# Inverting_LM741.net
KiCad netlist of a schematic drawn in EAGLE
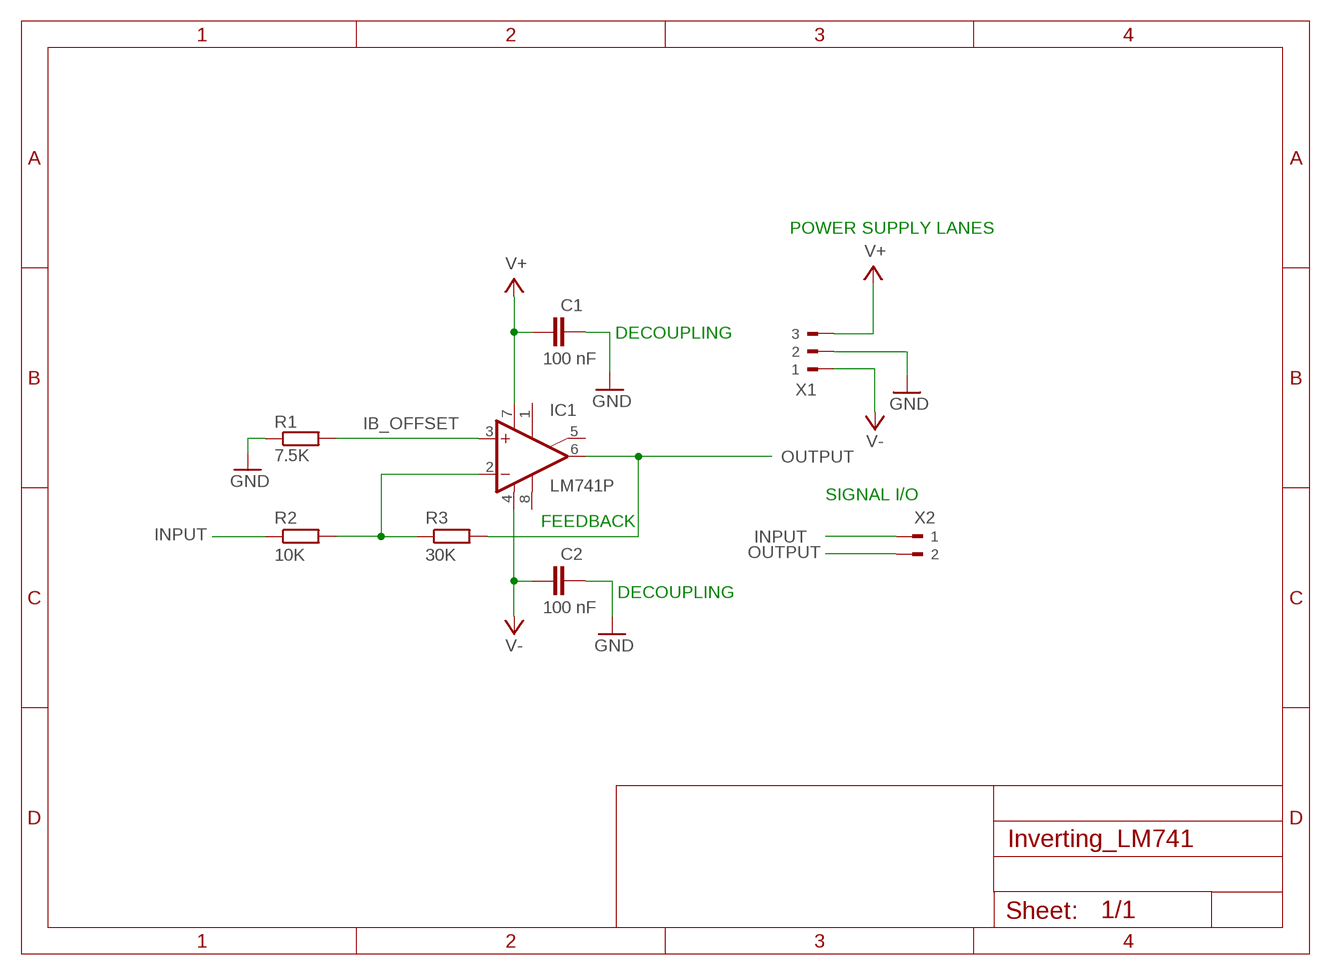
[diagram p0: schematic, sheet 1]

(export (version "E")
  (design (tool "Eeschema 10.0.6"))
  (components
    (comp (ref "C1")
      (value "100 nF")
      (footprint "eagle-import:C025-025X050")
      (libsource (lib "eagle-import") (part "C-EU025-025X050"))
    )
    (comp (ref "C2")
      (value "100 nF")
      (footprint "eagle-import:C025-025X050")
      (libsource (lib "eagle-import") (part "C-EU025-025X050"))
    )
    (comp (ref "IC1")
      (value "LM741P")
      (footprint "eagle-import:DIL08")
      (libsource (lib "eagle-import") (part "741PLM"))
    )
    (comp (ref "R1")
      (value "7.5K")
      (footprint "eagle-import:0207_10")
      (libsource (lib "eagle-import") (part "R-EU_0207/10"))
    )
    (comp (ref "R2")
      (value "10K")
      (footprint "eagle-import:0207_10")
      (libsource (lib "eagle-import") (part "R-EU_0207/10"))
    )
    (comp (ref "R3")
      (value "30K")
      (footprint "eagle-import:0207_10")
      (libsource (lib "eagle-import") (part "R-EU_0207/10"))
    )
    (comp (ref "X1")
      (value "90-3")
      (footprint "eagle-import:90-3")
      (libsource (lib "eagle-import") (part "90-3"))
    )
    (comp (ref "X2")
      (value "90-2")
      (footprint "eagle-import:90-2")
      (libsource (lib "eagle-import") (part "90-2"))
    )
  )
  (nets
    (net (code "1") (name "/IB_OFFSET") (class "Default")
      (node (ref "IC1") (pin "3") (pinfunction "+IN_3") (pintype "input"))
      (node (ref "R1") (pin "2") (pinfunction "2_2") (pintype "passive"))
    )
    (net (code "2") (name "/INPUT") (class "Default")
      (node (ref "R2") (pin "1") (pinfunction "1_1") (pintype "passive"))
      (node (ref "X2") (pin "1") (pinfunction "1_1") (pintype "passive"))
    )
    (net (code "3") (name "/OUTPUT") (class "Default")
      (node (ref "IC1") (pin "6") (pinfunction "OUT_6") (pintype "output"))
      (node (ref "R3") (pin "2") (pinfunction "2_2") (pintype "passive"))
      (node (ref "X2") (pin "2") (pinfunction "2_2") (pintype "passive"))
    )
    (net (code "4") (name "GND") (class "Default")
      (node (ref "C1") (pin "1") (pinfunction "1_1") (pintype "passive"))
      (node (ref "C2") (pin "1") (pinfunction "1_1") (pintype "passive"))
      (node (ref "R1") (pin "1") (pinfunction "1_1") (pintype "passive"))
      (node (ref "X1") (pin "2") (pinfunction "2_2") (pintype "passive"))
    )
    (net (code "5") (name "Net-(IC1--IN)") (class "Default")
      (node (ref "IC1") (pin "2") (pinfunction "-IN_2") (pintype "input"))
      (node (ref "R2") (pin "2") (pinfunction "2_2") (pintype "passive"))
      (node (ref "R3") (pin "1") (pinfunction "1_1") (pintype "passive"))
    )
    (net (code "6") (name "V+") (class "Default")
      (node (ref "C1") (pin "2") (pinfunction "2_2") (pintype "passive"))
      (node (ref "IC1") (pin "7") (pinfunction "V+_7") (pintype "power_in"))
      (node (ref "X1") (pin "3") (pinfunction "3_3") (pintype "passive"))
    )
    (net (code "7") (name "V-") (class "Default")
      (node (ref "C2") (pin "2") (pinfunction "2_2") (pintype "passive"))
      (node (ref "IC1") (pin "4") (pinfunction "V-_4") (pintype "power_in"))
      (node (ref "X1") (pin "1") (pinfunction "1_1") (pintype "passive"))
    )
    (net (code "8") (name "unconnected-(IC1-ON1-Pad1)") (class "Default")
      (node (ref "IC1") (pin "1") (pinfunction "ON1_1") (pintype "passive"))
    )
    (net (code "9") (name "unconnected-(IC1-ON2-Pad5)") (class "Default")
      (node (ref "IC1") (pin "5") (pinfunction "ON2_5") (pintype "passive"))
    )
    (net (code "10") (name "unconnected-(IC1-OPT-Pad8)") (class "Default")
      (node (ref "IC1") (pin "8") (pinfunction "OPT_8") (pintype "passive"))
    )
  )
)
